# LOKI-PSS-V1-r3_0.net
KiCad netlist of a schematic drawn in Altium Designer
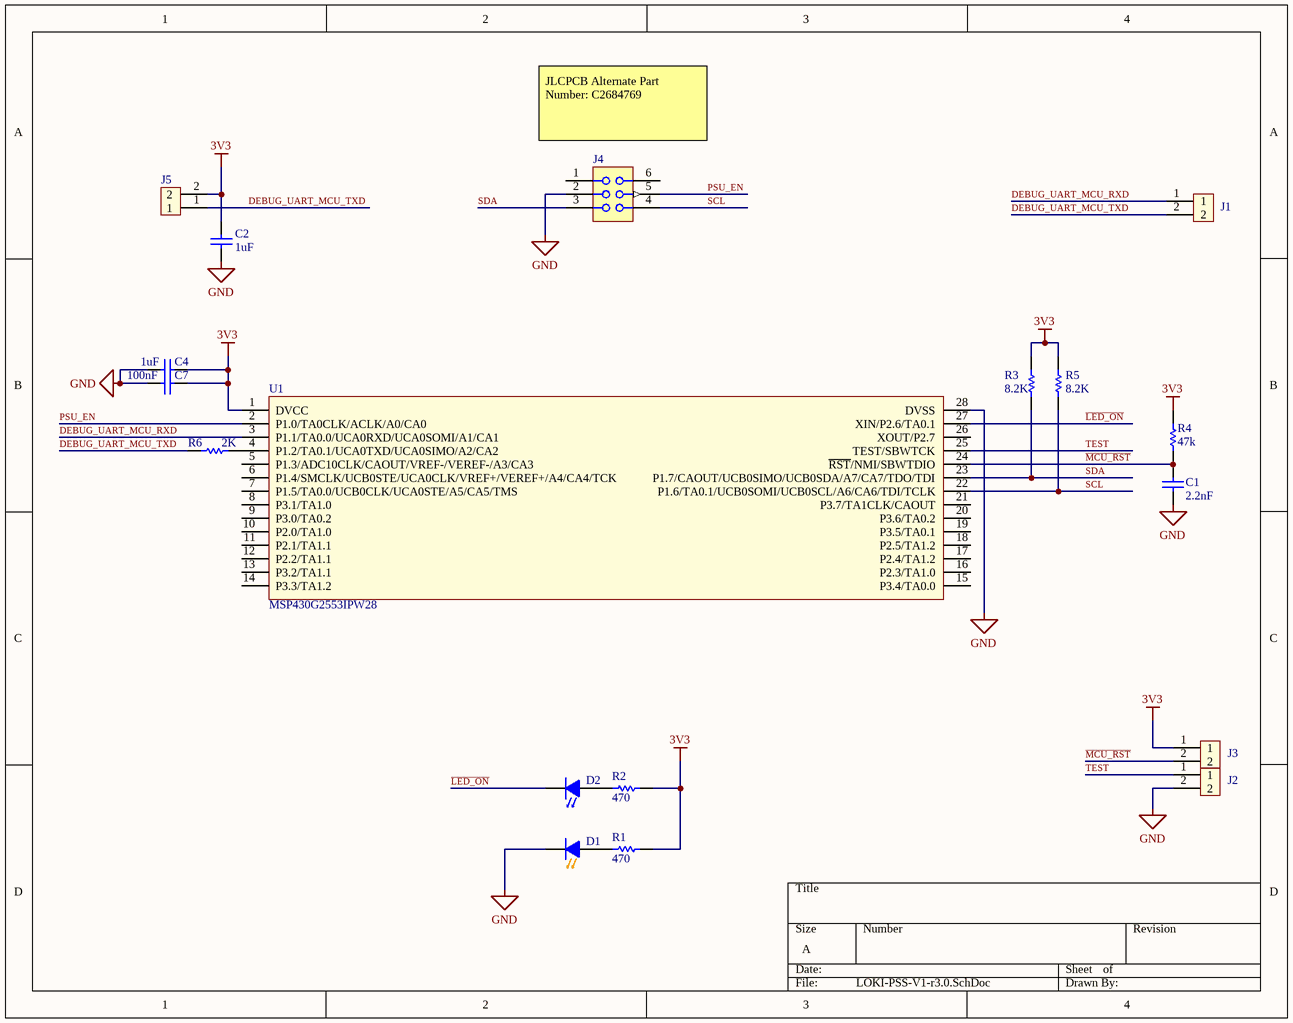
[diagram p0: LOKI-PSS-V1-r3.0.SchDoc]

(export (version "E")
  (design (tool "Eeschema 10.0.6"))
  (components
    (comp (ref "C1")
      (value "2.2nF")
      (footprint "C0402_BEI")
      (description "CAP CER 2200PF 50V 10% X7R 0402")
      (fields
        (field (name "PART NUMBER") "GRM155R71H222KA01D (2)")
        (field (name "MANUFACTURER") "Murata Electronics North America")
      )
      (libsource (lib "RS_General_LIB") (part "Cnonpol"))
    )
    (comp (ref "C2")
      (value "1uF")
      (footprint "C0402_L")
      (description "CAP CER 1UF 6.3V X5R 0402")
      (fields (field (name "PART NUMBER") "JMK105BJ105KV-F") (field (name "MANUFACTURER") "Taiyo Yuden"))
      (libsource (lib "RS_General_LIB") (part "Cnonpol"))
    )
    (comp (ref "C4")
      (value "1uF")
      (footprint "C0402_L")
      (description "CAP CER 1UF 6.3V X5R 0402")
      (fields (field (name "PART NUMBER") "JMK105BJ105KV-F") (field (name "MANUFACTURER") "Taiyo Yuden"))
      (libsource (lib "RS_General_LIB") (part "Cnonpol"))
    )
    (comp (ref "C7")
      (value "100nF")
      (footprint "C0402_BEI")
      (description "CAP CER 0.1UF 10V X5R 0402")
      (fields (field (name "PART NUMBER") "C1005X5R1A104K050BA") (field (name "OWLET PART NUMBER") "E0072"))
      (libsource (lib "RS_General_LIB") (part "Cnonpol"))
    )
    (comp (ref "D1")
      (value "LED-ORANGE")
      (footprint "LED0603_L_ORANGE")
      (description "Led Orange Clear 1608 SMD")
      (fields (field (name "PART NUMBER") "B1931UD--05D000314U1930") (field (name "MANUFACTURER") "Inolux"))
      (libsource (lib "RS_General_LIB") (part "LED-ORANGE"))
    )
    (comp (ref "D2")
      (value "LED-BLUE")
      (footprint "LED0603_L_BLUE")
      (description "Single Color LED, Ultra Bright Blue, Water Clear, 1.1mm")
      (fields (field (name "PART NUMBER") "LTST-C191TBKT") (field (name "MANUFACTURER") "Vishay Lite-On"))
      (libsource (lib "RS_General_LIB") (part "LED-BLUE"))
    )
    (comp (ref "J1")
      (value "Header_2POS")
      (footprint "H2_2.54mm_S_THOLE")
      (description "Conn Unshrouded Header HDR 2 POS 2.54mm Solder S Thru-Hole")
      (fields (field (name "PART NUMBER") "TSW-106-08-L-S-R"))
      (libsource (lib "RS_General_LIB") (part "Header_2POS"))
    )
    (comp (ref "J2")
      (value "Header_2POS")
      (footprint "H2_2.54mm_S_THOLE")
      (description "Conn Unshrouded Header HDR 2 POS 2.54mm Solder S Thru-Hole")
      (fields (field (name "PART NUMBER") "TSW-106-08-L-S-R"))
      (libsource (lib "RS_General_LIB") (part "Header_2POS"))
    )
    (comp (ref "J3")
      (value "Header_2POS")
      (footprint "H2_2.54mm_S_THOLE")
      (description "Conn Unshrouded Header HDR 2 POS 2.54mm Solder S Thru-Hole")
      (fields (field (name "PART NUMBER") "TSW-106-08-L-S-R"))
      (libsource (lib "RS_General_LIB") (part "Header_2POS"))
    )
    (comp (ref "J4")
      (value "2x3 Connector")
      (footprint "BF100-06-X-X-1-0640")
      (description "6POS, 2MM PITCH SOCKET, DIL, SMT")
      (fields (field (name "PART NUMBER") "BF100-06-A-D-0-0640-L-C"))
      (libsource (lib "RS_General_LIB") (part "2x3 Connector"))
    )
    (comp (ref "J5")
      (value "Header_2POS")
      (footprint "2POS_RA_TH")
      (description "Conn Unshrouded Header HDR 2 POS 2.54mm Solder RA Thru-Hole")
      (fields (field (name "PART NUMBER") "PH1RB-02-UA") (field (name "MANUFACTURER") "Adam Equipment"))
      (libsource (lib "") (part "Header_2POS_1"))
    )
    (comp (ref "R1")
      (value "470")
      (footprint "R0402_L")
      (description "RES 470 OHM 1/10W 1% 0402 SMD")
      (fields (field (name "PART NUMBER") "ERJ-2RKF4700X") (field (name "MANUFACTURER") "Panasonic - ECG"))
      (libsource (lib "RS_General_LIB") (part "R8"))
    )
    (comp (ref "R2")
      (value "470")
      (footprint "R0402_L")
      (description "RES 470 OHM 1/10W 1% 0402 SMD")
      (fields (field (name "PART NUMBER") "ERJ-2RKF4700X") (field (name "MANUFACTURER") "Panasonic - ECG"))
      (libsource (lib "RS_General_LIB") (part "R8"))
    )
    (comp (ref "R3")
      (value "8.2K")
      (footprint "R0402_L")
      (description "RES 8.20K OHM 1/10W 1% 0402 SMD")
      (fields (field (name "PART NUMBER") "ERJ-2RKF8201X") (field (name "MANUFACTURER") "Panasonic - ECG"))
      (libsource (lib "RS_General_LIB") (part "R12"))
    )
    (comp (ref "R4")
      (value "47k")
      (footprint "R0402_BEI")
      (description "RES SMD 47K OHM 5% 1/10W 0402")
      (fields (field (name "PART NUMBER") "ERJ-2GEJ473X (2)") (field (name "OWLET PART NUMBER") "E0067"))
      (libsource (lib "RS_General_LIB") (part "Rgeneric"))
    )
    (comp (ref "R5")
      (value "8.2K")
      (footprint "R0402_L")
      (description "RES 8.20K OHM 1/10W 1% 0402 SMD")
      (fields (field (name "PART NUMBER") "ERJ-2RKF8201X") (field (name "MANUFACTURER") "Panasonic - ECG"))
      (libsource (lib "RS_General_LIB") (part "R12"))
    )
    (comp (ref "R6")
      (value "2K")
      (footprint "R0402_L")
      (description "RES 2.0K OHM 1/16W 5% 0402 SMD")
      (fields (field (name "PART NUMBER") "RC0402JR-072KL") (field (name "MANUFACTURER") "Yageo"))
      (libsource (lib "RS_General_LIB") (part "R2K"))
    )
    (comp (ref "U1")
      (value "MSP430G2553IPW28")
      (footprint "28-TSSOP_L")
      (description "MSP430 MSP430G2xx Microcontroller IC 16-Bit 16MHz 16KB (16K x 8) FLASH 28-TSSOP")
      (fields
        (field (name "PART NUMBER") "MSP430G2553IPW28R")
        (field (name "MANUFACTURER") "Texas Instruments")
      )
      (libsource (lib "RS_General_LIB") (part "MSP430G2553IPW28"))
    )
  )
  (nets
    (net (code "1") (name "/DEBUG_UART_MCU_RXD") (class "Default")
      (node (ref "J1") (pin "1") (pinfunction "1_1") (pintype "passive"))
      (node (ref "U1") (pin "3") (pinfunction "P1.1/TA0.0/UCA0RXD/UCA0SOMI/A1/CA1_3") (pintype "passive"))
    )
    (net (code "2") (name "/DEBUG_UART_MCU_TXD") (class "Default")
      (node (ref "J1") (pin "2") (pinfunction "2_2") (pintype "passive"))
      (node (ref "J5") (pin "1") (pinfunction "1_1") (pintype "passive"))
      (node (ref "R6") (pin "1") (pinfunction "1_1") (pintype "passive"))
    )
    (net (code "3") (name "/PSU_EN") (class "Default")
      (node (ref "J4") (pin "5") (pintype "output"))
      (node (ref "U1") (pin "2") (pinfunction "P1.0/TA0CLK/ACLK/A0/CA0_2") (pintype "passive"))
    )
    (net (code "4") (name "/SCL") (class "Default")
      (node (ref "J4") (pin "4") (pintype "passive"))
      (node (ref "R5") (pin "1") (pinfunction "1_1") (pintype "passive"))
      (node (ref "U1") (pin "22") (pinfunction "P1.6/TA0.1/UCB0SOMI/UCB0SCL/A6/CA6/TDI/TCLK_22") (pintype "passive"))
    )
    (net (code "5") (name "/SDA") (class "Default")
      (node (ref "J4") (pin "3") (pintype "passive"))
      (node (ref "R3") (pin "1") (pinfunction "1_1") (pintype "passive"))
      (node (ref "U1") (pin "23") (pinfunction "P1.7/CAOUT/UCB0SIMO/UCB0SDA/A7/CA7/TDO/TDI_23") (pintype "passive"))
    )
    (net (code "6") (name "/TEST") (class "Default")
      (node (ref "J2") (pin "1") (pinfunction "1_1") (pintype "passive"))
      (node (ref "U1") (pin "25") (pinfunction "TEST/SBWTCK_25") (pintype "passive"))
    )
    (net (code "7") (name "/~{LED_ON}") (class "Default")
      (node (ref "D2") (pin "2") (pinfunction "K_2") (pintype "passive"))
      (node (ref "U1") (pin "27") (pinfunction "XIN/P2.6/TA0.1_27") (pintype "passive"))
    )
    (net (code "8") (name "/~{MCU_RST}") (class "Default")
      (node (ref "C1") (pin "2") (pinfunction "2_2") (pintype "passive"))
      (node (ref "J3") (pin "2") (pinfunction "2_2") (pintype "passive"))
      (node (ref "R4") (pin "1") (pinfunction "1_1") (pintype "passive"))
      (node (ref "U1") (pin "24") (pinfunction "~{RST}/NMI/SBWTDIO_24") (pintype "passive"))
    )
    (net (code "9") (name "3V3") (class "Default")
      (node (ref "C2") (pin "2") (pinfunction "2_2") (pintype "passive"))
      (node (ref "C4") (pin "2") (pinfunction "2_2") (pintype "passive"))
      (node (ref "C7") (pin "2") (pinfunction "2_2") (pintype "passive"))
      (node (ref "J3") (pin "1") (pinfunction "1_1") (pintype "passive"))
      (node (ref "J5") (pin "2") (pinfunction "2_2") (pintype "passive"))
      (node (ref "R1") (pin "2") (pinfunction "2_2") (pintype "passive"))
      (node (ref "R2") (pin "2") (pinfunction "2_2") (pintype "passive"))
      (node (ref "R3") (pin "2") (pinfunction "2_2") (pintype "passive"))
      (node (ref "R4") (pin "2") (pinfunction "2_2") (pintype "passive"))
      (node (ref "R5") (pin "2") (pinfunction "2_2") (pintype "passive"))
      (node (ref "U1") (pin "1") (pinfunction "DVCC_1") (pintype "passive"))
    )
    (net (code "10") (name "GND") (class "Default")
      (node (ref "C1") (pin "1") (pinfunction "1_1") (pintype "passive"))
      (node (ref "C2") (pin "1") (pinfunction "1_1") (pintype "passive"))
      (node (ref "C4") (pin "1") (pinfunction "1_1") (pintype "passive"))
      (node (ref "C7") (pin "1") (pinfunction "1_1") (pintype "passive"))
      (node (ref "D1") (pin "2") (pinfunction "K_2") (pintype "passive"))
      (node (ref "J2") (pin "2") (pinfunction "2_2") (pintype "passive"))
      (node (ref "J4") (pin "2") (pintype "passive"))
      (node (ref "U1") (pin "28") (pinfunction "DVSS_28") (pintype "passive"))
    )
    (net (code "11") (name "Net-(D1-A)") (class "Default")
      (node (ref "D1") (pin "1") (pinfunction "A_1") (pintype "passive"))
      (node (ref "R1") (pin "1") (pinfunction "1_1") (pintype "passive"))
    )
    (net (code "12") (name "Net-(D2-A)") (class "Default")
      (node (ref "D2") (pin "1") (pinfunction "A_1") (pintype "passive"))
      (node (ref "R2") (pin "1") (pinfunction "1_1") (pintype "passive"))
    )
    (net (code "13") (name "Net-(U1-P1.2{slash}TA0.1{slash}UCA0TXD{slash}UCA0SIMO{slash}A2{slash}CA2)") (class "Default")
      (node (ref "R6") (pin "2") (pinfunction "2_2") (pintype "passive"))
      (node (ref "U1") (pin "4") (pinfunction "P1.2/TA0.1/UCA0TXD/UCA0SIMO/A2/CA2_4") (pintype "passive"))
    )
    (net (code "14") (name "unconnected-(J4-Pad1)") (class "Default")
      (node (ref "J4") (pin "1") (pintype "passive"))
    )
    (net (code "15") (name "unconnected-(J4-Pad6)") (class "Default")
      (node (ref "J4") (pin "6") (pintype "passive"))
    )
    (net (code "16") (name "unconnected-(U1-P1.3{slash}ADC10CLK{slash}CAOUT{slash}VREF-{slash}VEREF-{slash}A3{slash}CA3-Pad5)") (class "Default")
      (node (ref "U1") (pin "5") (pinfunction "P1.3/ADC10CLK/CAOUT/VREF-/VEREF-/A3/CA3_5") (pintype "passive"))
    )
    (net (code "17") (name "unconnected-(U1-P1.4{slash}SMCLK{slash}UCB0STE{slash}UCA0CLK{slash}VREF+{slash}VEREF+{slash}A4{slash}CA4{slash}TCK-Pad6)") (class "Default")
      (node (ref "U1") (pin "6") (pinfunction "P1.4/SMCLK/UCB0STE/UCA0CLK/VREF+/VEREF+/A4/CA4/TCK_6") (pintype "passive"))
    )
    (net (code "18") (name "unconnected-(U1-P1.5{slash}TA0.0{slash}UCB0CLK{slash}UCA0STE{slash}A5{slash}CA5{slash}TMS-Pad7)") (class "Default")
      (node (ref "U1") (pin "7") (pinfunction "P1.5/TA0.0/UCB0CLK/UCA0STE/A5/CA5/TMS_7") (pintype "passive"))
    )
    (net (code "19") (name "unconnected-(U1-P2.0{slash}TA1.0-Pad10)") (class "Default")
      (node (ref "U1") (pin "10") (pinfunction "P2.0/TA1.0_10") (pintype "passive"))
    )
    (net (code "20") (name "unconnected-(U1-P2.1{slash}TA1.1-Pad11)") (class "Default")
      (node (ref "U1") (pin "11") (pinfunction "P2.1/TA1.1_11") (pintype "passive"))
    )
    (net (code "21") (name "unconnected-(U1-P2.2{slash}TA1.1-Pad12)") (class "Default")
      (node (ref "U1") (pin "12") (pinfunction "P2.2/TA1.1_12") (pintype "passive"))
    )
    (net (code "22") (name "unconnected-(U1-P2.3{slash}TA1.0-Pad16)") (class "Default")
      (node (ref "U1") (pin "16") (pinfunction "P2.3/TA1.0_16") (pintype "passive"))
    )
    (net (code "23") (name "unconnected-(U1-P2.4{slash}TA1.2-Pad17)") (class "Default")
      (node (ref "U1") (pin "17") (pinfunction "P2.4/TA1.2_17") (pintype "passive"))
    )
    (net (code "24") (name "unconnected-(U1-P2.5{slash}TA1.2-Pad18)") (class "Default")
      (node (ref "U1") (pin "18") (pinfunction "P2.5/TA1.2_18") (pintype "passive"))
    )
    (net (code "25") (name "unconnected-(U1-P3.0{slash}TA0.2-Pad9)") (class "Default")
      (node (ref "U1") (pin "9") (pinfunction "P3.0/TA0.2_9") (pintype "passive"))
    )
    (net (code "26") (name "unconnected-(U1-P3.1{slash}TA1.0-Pad8)") (class "Default")
      (node (ref "U1") (pin "8") (pinfunction "P3.1/TA1.0_8") (pintype "passive"))
    )
    (net (code "27") (name "unconnected-(U1-P3.2{slash}TA1.1-Pad13)") (class "Default")
      (node (ref "U1") (pin "13") (pinfunction "P3.2/TA1.1_13") (pintype "passive"))
    )
    (net (code "28") (name "unconnected-(U1-P3.3{slash}TA1.2-Pad14)") (class "Default")
      (node (ref "U1") (pin "14") (pinfunction "P3.3/TA1.2_14") (pintype "passive"))
    )
    (net (code "29") (name "unconnected-(U1-P3.4{slash}TA0.0-Pad15)") (class "Default")
      (node (ref "U1") (pin "15") (pinfunction "P3.4/TA0.0_15") (pintype "passive"))
    )
    (net (code "30") (name "unconnected-(U1-P3.5{slash}TA0.1-Pad19)") (class "Default")
      (node (ref "U1") (pin "19") (pinfunction "P3.5/TA0.1_19") (pintype "passive"))
    )
    (net (code "31") (name "unconnected-(U1-P3.6{slash}TA0.2-Pad20)") (class "Default")
      (node (ref "U1") (pin "20") (pinfunction "P3.6/TA0.2_20") (pintype "passive"))
    )
    (net (code "32") (name "unconnected-(U1-P3.7{slash}TA1CLK{slash}CAOUT-Pad21)") (class "Default")
      (node (ref "U1") (pin "21") (pinfunction "P3.7/TA1CLK/CAOUT_21") (pintype "passive"))
    )
    (net (code "33") (name "unconnected-(U1-XOUT{slash}P2.7-Pad26)") (class "Default")
      (node (ref "U1") (pin "26") (pinfunction "XOUT/P2.7_26") (pintype "passive"))
    )
  )
)
